# iPad_adapt_board.net
KiCad netlist of a schematic drawn in EAGLE
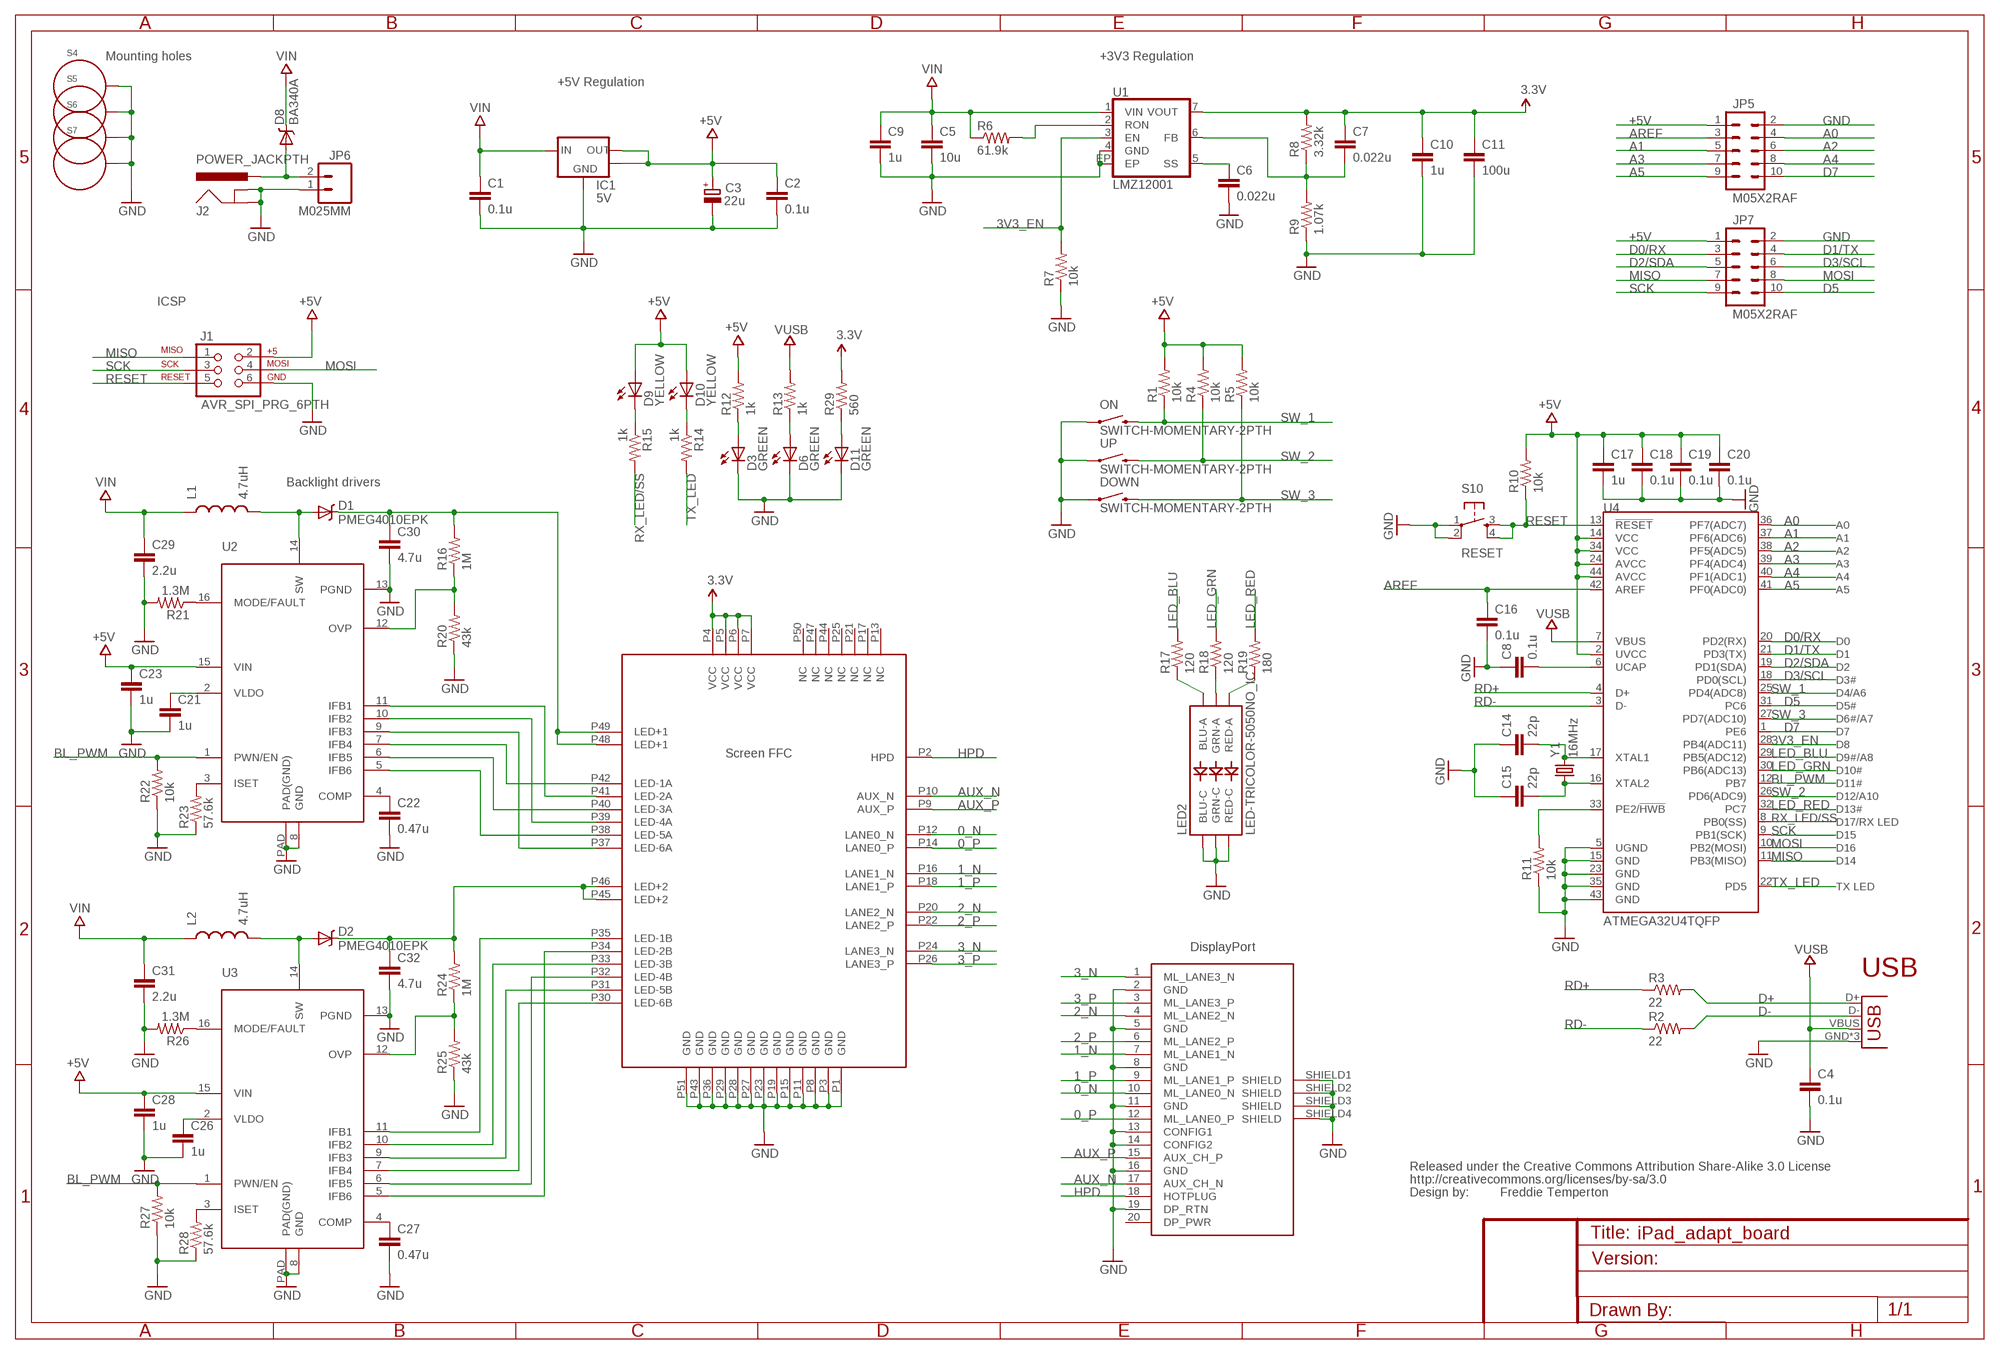
[diagram p0: schematic, sheet 1]

(export (version "E")
  (design (tool "Eeschema 10.0.6"))
  (components
    (comp (ref "C1")
      (value "0.1u")
      (footprint "eagle-import:0603-CAP")
      (libsource (lib "eagle-import") (part "SparkFun-Passives_CAP0603-CAP"))
    )
    (comp (ref "C2")
      (value "0.1u")
      (footprint "eagle-import:0603-CAP")
      (libsource (lib "eagle-import") (part "SparkFun-Passives_CAP0603-CAP"))
    )
    (comp (ref "C3")
      (value "22u")
      (footprint "eagle-import:SMC_B")
      (libsource (lib "eagle-import") (part "CPOL-EUSMCB"))
    )
    (comp (ref "C4")
      (value "0.1u")
      (footprint "eagle-import:0603-CAP")
      (libsource (lib "eagle-import") (part "SparkFun-Passives_CAP0603-CAP"))
    )
    (comp (ref "C5")
      (value "10u")
      (footprint "eagle-import:1206")
      (libsource (lib "eagle-import") (part "CAP1206"))
    )
    (comp (ref "C6")
      (value "0.022u")
      (footprint "eagle-import:0603-CAP")
      (libsource (lib "eagle-import") (part "SparkFun-Passives_CAP0603-CAP"))
    )
    (comp (ref "C7")
      (value "0.022u")
      (footprint "eagle-import:0603-CAP")
      (libsource (lib "eagle-import") (part "SparkFun-Passives_CAP0603-CAP"))
    )
    (comp (ref "C8")
      (value "0.1u")
      (footprint "eagle-import:0603-CAP")
      (libsource (lib "eagle-import") (part "SparkFun-Passives_CAP0603-CAP"))
    )
    (comp (ref "C9")
      (value "1u")
      (footprint "eagle-import:1206")
      (libsource (lib "eagle-import") (part "CAP1206"))
    )
    (comp (ref "C10")
      (value "1u")
      (footprint "eagle-import:1206")
      (libsource (lib "eagle-import") (part "CAP1206"))
    )
    (comp (ref "C11")
      (value "100u")
      (footprint "eagle-import:C1210")
      (libsource (lib "eagle-import") (part "C-EUC1210"))
    )
    (comp (ref "C14")
      (value "22p")
      (footprint "eagle-import:0603-CAP")
      (libsource (lib "eagle-import") (part "SparkFun-Passives_CAP0603-CAP"))
    )
    (comp (ref "C15")
      (value "22p")
      (footprint "eagle-import:0603-CAP")
      (libsource (lib "eagle-import") (part "SparkFun-Passives_CAP0603-CAP"))
    )
    (comp (ref "C16")
      (value "0.1u")
      (footprint "eagle-import:0603-CAP")
      (libsource (lib "eagle-import") (part "SparkFun-Passives_CAP0603-CAP"))
    )
    (comp (ref "C17")
      (value "1u")
      (footprint "eagle-import:0603-CAP")
      (libsource (lib "eagle-import") (part "SparkFun-Passives_CAP0603-CAP"))
    )
    (comp (ref "C18")
      (value "0.1u")
      (footprint "eagle-import:0603-CAP")
      (libsource (lib "eagle-import") (part "SparkFun-Passives_CAP0603-CAP"))
    )
    (comp (ref "C19")
      (value "0.1u")
      (footprint "eagle-import:0603-CAP")
      (libsource (lib "eagle-import") (part "SparkFun-Passives_CAP0603-CAP"))
    )
    (comp (ref "C20")
      (value "0.1u")
      (footprint "eagle-import:0603-CAP")
      (libsource (lib "eagle-import") (part "SparkFun-Passives_CAP0603-CAP"))
    )
    (comp (ref "C21")
      (value "1u")
      (footprint "eagle-import:0603-CAP")
      (libsource (lib "eagle-import") (part "SparkFun-Passives_CAP0603-CAP"))
    )
    (comp (ref "C22")
      (value "0.47u")
      (footprint "eagle-import:0603-CAP")
      (libsource (lib "eagle-import") (part "SparkFun-Passives_CAP0603-CAP"))
    )
    (comp (ref "C23")
      (value "1u")
      (footprint "eagle-import:0603-CAP")
      (libsource (lib "eagle-import") (part "SparkFun-Passives_CAP0603-CAP"))
    )
    (comp (ref "C26")
      (value "1u")
      (footprint "eagle-import:0603-CAP")
      (libsource (lib "eagle-import") (part "SparkFun-Passives_CAP0603-CAP"))
    )
    (comp (ref "C27")
      (value "0.47u")
      (footprint "eagle-import:0603-CAP")
      (libsource (lib "eagle-import") (part "SparkFun-Passives_CAP0603-CAP"))
    )
    (comp (ref "C28")
      (value "1u")
      (footprint "eagle-import:0603-CAP")
      (libsource (lib "eagle-import") (part "SparkFun-Passives_CAP0603-CAP"))
    )
    (comp (ref "C29")
      (value "2.2u")
      (footprint "eagle-import:0805")
      (libsource (lib "eagle-import") (part "CAP0805"))
    )
    (comp (ref "C30")
      (value "4.7u")
      (footprint "eagle-import:0805")
      (libsource (lib "eagle-import") (part "CAP0805"))
    )
    (comp (ref "C31")
      (value "2.2u")
      (footprint "eagle-import:0805")
      (libsource (lib "eagle-import") (part "CAP0805"))
    )
    (comp (ref "C32")
      (value "4.7u")
      (footprint "eagle-import:0805")
      (libsource (lib "eagle-import") (part "CAP0805"))
    )
    (comp (ref "CC_TEXT1")
      (value "CREATIVE_COMMONS")
      (footprint "eagle-import:CREATIVE_COMMONS")
      (libsource (lib "eagle-import") (part "CREATIVE_COMMONS"))
    )
    (comp (ref "D1")
      (value "PMEG4010EPK")
      (footprint "eagle-import:SOD1608")
      (libsource (lib "eagle-import") (part "PMEG4010EPK"))
    )
    (comp (ref "D2")
      (value "PMEG4010EPK")
      (footprint "eagle-import:SOD1608")
      (libsource (lib "eagle-import") (part "PMEG4010EPK"))
    )
    (comp (ref "D3")
      (value "GREEN")
      (footprint "eagle-import:LED-0603")
      (libsource (lib "eagle-import") (part "LED-GREEN0603"))
    )
    (comp (ref "D6")
      (value "GREEN")
      (footprint "eagle-import:LED-0603")
      (libsource (lib "eagle-import") (part "LED-GREEN0603"))
    )
    (comp (ref "D8")
      (value "BA340A")
      (footprint "eagle-import:SMA-DIODE")
      (libsource (lib "eagle-import") (part "B340A"))
    )
    (comp (ref "D9")
      (value "YELLOW")
      (footprint "eagle-import:LED-0603")
      (libsource (lib "eagle-import") (part "LED-YELLOW0603"))
    )
    (comp (ref "D10")
      (value "YELLOW")
      (footprint "eagle-import:LED-0603")
      (libsource (lib "eagle-import") (part "LED-YELLOW0603"))
    )
    (comp (ref "D11")
      (value "GREEN")
      (footprint "eagle-import:LED-0603")
      (libsource (lib "eagle-import") (part "LED-GREEN0603"))
    )
    (comp (ref "DOWN")
      (value "SWITCH-MOMENTARY-2PTH")
      (footprint "eagle-import:TACTILE-PTH")
      (libsource (lib "eagle-import") (part "SWITCH-MOMENTARY-2PTH"))
    )
    (comp (ref "IC1")
      (value "5V")
      (footprint "eagle-import:SOT223")
      (libsource (lib "eagle-import") (part "V_REG_LM1117SOT223"))
    )
    (comp (ref "J1")
      (value "AVR_SPI_PRG_6PTH")
      (footprint "eagle-import:2X3")
      (libsource (lib "eagle-import") (part "AVR_SPI_PRG_6PTH"))
    )
    (comp (ref "J2")
      (value "POWER_JACKPTH")
      (footprint "eagle-import:POWER_JACK_PTH")
      (libsource (lib "eagle-import") (part "POWER_JACKPTH"))
    )
    (comp (ref "J3") (value "DP") (footprint "eagle-import:DP") (libsource (lib "eagle-import") (part "DP")))
    (comp (ref "J4")
      (value "IPAD3-CONN")
      (footprint "eagle-import:MOLEX502250-5191")
      (libsource (lib "eagle-import") (part "IPAD3-CONN"))
    )
    (comp (ref "JP1")
      (value "USB-MICROB")
      (footprint "eagle-import:USB-MICROB")
      (libsource (lib "eagle-import") (part "USB-MICROB"))
    )
    (comp (ref "JP5")
      (value "M05X2RAF")
      (footprint "eagle-import:2X5-RAF")
      (libsource (lib "eagle-import") (part "M05X2RAF"))
    )
    (comp (ref "JP6")
      (value "M025MM")
      (footprint "eagle-import:SCREWTERMINAL-5MM-2")
      (libsource (lib "eagle-import") (part "M025MM"))
    )
    (comp (ref "JP7")
      (value "M05X2RAF")
      (footprint "eagle-import:2X5-RAF")
      (libsource (lib "eagle-import") (part "M05X2RAF"))
    )
    (comp (ref "L1")
      (value "4.7uH")
      (footprint "eagle-import:SRN6045")
      (libsource (lib "eagle-import") (part "INDUCTORBOURNS_SRN6045"))
    )
    (comp (ref "L2")
      (value "4.7uH")
      (footprint "eagle-import:SRN6045")
      (libsource (lib "eagle-import") (part "INDUCTORBOURNS_SRN6045"))
    )
    (comp (ref "LED2")
      (value "LED-TRICOLOR-5050NO_IC")
      (footprint "eagle-import:LED-TRICOLOR-5050")
      (libsource (lib "eagle-import") (part "LED-TRICOLOR-5050NO_IC"))
    )
    (comp (ref "ON")
      (value "SWITCH-MOMENTARY-2PTH")
      (footprint "eagle-import:TACTILE-PTH")
      (libsource (lib "eagle-import") (part "SWITCH-MOMENTARY-2PTH"))
    )
    (comp (ref "R1")
      (value "10k")
      (footprint "eagle-import:0603-RES")
      (libsource (lib "eagle-import") (part "RESISTOR0603-RES"))
    )
    (comp (ref "R2")
      (value "22")
      (footprint "eagle-import:0603-RES")
      (libsource (lib "eagle-import") (part "RESISTOR0603-RES"))
    )
    (comp (ref "R3")
      (value "22")
      (footprint "eagle-import:0603-RES")
      (libsource (lib "eagle-import") (part "RESISTOR0603-RES"))
    )
    (comp (ref "R4")
      (value "10k")
      (footprint "eagle-import:0603-RES")
      (libsource (lib "eagle-import") (part "RESISTOR0603-RES"))
    )
    (comp (ref "R5")
      (value "10k")
      (footprint "eagle-import:0603-RES")
      (libsource (lib "eagle-import") (part "RESISTOR0603-RES"))
    )
    (comp (ref "R6")
      (value "61.9k")
      (footprint "eagle-import:0603-RES")
      (libsource (lib "eagle-import") (part "RESISTOR0603-RES"))
    )
    (comp (ref "R7")
      (value "10k")
      (footprint "eagle-import:0603-RES")
      (libsource (lib "eagle-import") (part "RESISTOR0603-RES"))
    )
    (comp (ref "R8")
      (value "3.32k")
      (footprint "eagle-import:0603-RES")
      (libsource (lib "eagle-import") (part "RESISTOR0603-RES"))
    )
    (comp (ref "R9")
      (value "1.07k")
      (footprint "eagle-import:0603-RES")
      (libsource (lib "eagle-import") (part "RESISTOR0603-RES"))
    )
    (comp (ref "R10")
      (value "10k")
      (footprint "eagle-import:0603-RES")
      (libsource (lib "eagle-import") (part "RESISTOR0603-RES"))
    )
    (comp (ref "R11")
      (value "10k")
      (footprint "eagle-import:0603-RES")
      (libsource (lib "eagle-import") (part "RESISTOR0603-RES"))
    )
    (comp (ref "R12")
      (value "1k")
      (footprint "eagle-import:0603-RES")
      (libsource (lib "eagle-import") (part "RESISTOR0603-RES"))
    )
    (comp (ref "R13")
      (value "1k")
      (footprint "eagle-import:0603-RES")
      (libsource (lib "eagle-import") (part "RESISTOR0603-RES"))
    )
    (comp (ref "R14")
      (value "1k")
      (footprint "eagle-import:0603-RES")
      (libsource (lib "eagle-import") (part "RESISTOR0603-RES"))
    )
    (comp (ref "R15")
      (value "1k")
      (footprint "eagle-import:0603-RES")
      (libsource (lib "eagle-import") (part "RESISTOR0603-RES"))
    )
    (comp (ref "R16")
      (value "1M")
      (footprint "eagle-import:0603-RES")
      (libsource (lib "eagle-import") (part "RESISTOR0603-RES"))
    )
    (comp (ref "R17")
      (value "120")
      (footprint "eagle-import:0603-RES")
      (libsource (lib "eagle-import") (part "RESISTOR0603-RES"))
    )
    (comp (ref "R18")
      (value "120")
      (footprint "eagle-import:0603-RES")
      (libsource (lib "eagle-import") (part "RESISTOR0603-RES"))
    )
    (comp (ref "R19")
      (value "180")
      (footprint "eagle-import:0603-RES")
      (libsource (lib "eagle-import") (part "RESISTOR0603-RES"))
    )
    (comp (ref "R20")
      (value "43k")
      (footprint "eagle-import:0603-RES")
      (libsource (lib "eagle-import") (part "RESISTOR0603-RES"))
    )
    (comp (ref "R21")
      (value "1.3M")
      (footprint "eagle-import:0603-RES")
      (libsource (lib "eagle-import") (part "RESISTOR0603-RES"))
    )
    (comp (ref "R22")
      (value "10k")
      (footprint "eagle-import:0603-RES")
      (libsource (lib "eagle-import") (part "RESISTOR0603-RES"))
    )
    (comp (ref "R23")
      (value "57.6k")
      (footprint "eagle-import:0603-RES")
      (libsource (lib "eagle-import") (part "RESISTOR0603-RES"))
    )
    (comp (ref "R24")
      (value "1M")
      (footprint "eagle-import:0603-RES")
      (libsource (lib "eagle-import") (part "RESISTOR0603-RES"))
    )
    (comp (ref "R25")
      (value "43k")
      (footprint "eagle-import:0603-RES")
      (libsource (lib "eagle-import") (part "RESISTOR0603-RES"))
    )
    (comp (ref "R26")
      (value "1.3M")
      (footprint "eagle-import:0603-RES")
      (libsource (lib "eagle-import") (part "RESISTOR0603-RES"))
    )
    (comp (ref "R27")
      (value "10k")
      (footprint "eagle-import:0603-RES")
      (libsource (lib "eagle-import") (part "RESISTOR0603-RES"))
    )
    (comp (ref "R28")
      (value "57.6k")
      (footprint "eagle-import:0603-RES")
      (libsource (lib "eagle-import") (part "RESISTOR0603-RES"))
    )
    (comp (ref "R29")
      (value "560")
      (footprint "eagle-import:0603-RES")
      (libsource (lib "eagle-import") (part "RESISTOR0603-RES"))
    )
    (comp (ref "S4")
      (value "STANDOFF_ELECTRICAL")
      (footprint "eagle-import:STANDOFF-ELECTRICAL")
      (libsource (lib "eagle-import") (part "STANDOFF_ELECTRICAL"))
    )
    (comp (ref "S5")
      (value "STANDOFF_ELECTRICAL")
      (footprint "eagle-import:STANDOFF-ELECTRICAL")
      (libsource (lib "eagle-import") (part "STANDOFF_ELECTRICAL"))
    )
    (comp (ref "S6")
      (value "STANDOFF_ELECTRICAL")
      (footprint "eagle-import:STANDOFF-ELECTRICAL")
      (libsource (lib "eagle-import") (part "STANDOFF_ELECTRICAL"))
    )
    (comp (ref "S7")
      (value "STANDOFF_ELECTRICAL")
      (footprint "eagle-import:STANDOFF-ELECTRICAL")
      (libsource (lib "eagle-import") (part "STANDOFF_ELECTRICAL"))
    )
    (comp (ref "S10")
      (value "RESET")
      (footprint "eagle-import:TACTILE_SWITCH_SMD")
      (libsource (lib "eagle-import") (part "TAC_SWITCHSMD"))
    )
    (comp (ref "U1")
      (value "LMZ12001")
      (footprint "eagle-import:TO-PMOD-7")
      (libsource (lib "eagle-import") (part "LMZ14203"))
    )
    (comp (ref "U2")
      (value "TPS61176")
      (footprint "eagle-import:QFN16")
      (libsource (lib "eagle-import") (part "TPS61176"))
    )
    (comp (ref "U3")
      (value "TPS61176")
      (footprint "eagle-import:QFN16")
      (libsource (lib "eagle-import") (part "TPS61176"))
    )
    (comp (ref "U4")
      (value "ATMEGA32U4TQFP")
      (footprint "eagle-import:SPARKFUN-DIGITALIC_TQFP44")
      (libsource (lib "eagle-import") (part "ATMEGA32U4TQFP"))
    )
    (comp (ref "UP")
      (value "SWITCH-MOMENTARY-2PTH")
      (footprint "eagle-import:TACTILE-PTH")
      (libsource (lib "eagle-import") (part "SWITCH-MOMENTARY-2PTH"))
    )
    (comp (ref "Y1")
      (value "16MHz")
      (footprint "eagle-import:CRYSTAL-TXC-7A")
      (libsource (lib "eagle-import") (part "CRYSTALTXC-7A"))
    )
  )
  (nets
    (net (code "1") (name "+5V") (class "Default")
      (node (ref "C17") (pin "1") (pinfunction "1_1") (pintype "passive"))
      (node (ref "C18") (pin "1") (pinfunction "1_1") (pintype "passive"))
      (node (ref "C19") (pin "1") (pinfunction "1_1") (pintype "passive"))
      (node (ref "C2") (pin "1") (pinfunction "1_1") (pintype "passive"))
      (node (ref "C20") (pin "1") (pinfunction "1_1") (pintype "passive"))
      (node (ref "C23") (pin "1") (pinfunction "1_1") (pintype "passive"))
      (node (ref "C28") (pin "1") (pinfunction "1_1") (pintype "passive"))
      (node (ref "C3") (pin "+") (pinfunction "+_+") (pintype "passive"))
      (node (ref "D10") (pin "A") (pinfunction "A_A") (pintype "passive"))
      (node (ref "D9") (pin "A") (pinfunction "A_A") (pintype "passive"))
      (node (ref "IC1") (pin "2") (pinfunction "OUT_2") (pintype "power_in"))
      (node (ref "IC1") (pin "4") (pinfunction "OUT_4") (pintype "power_in"))
      (node (ref "J1") (pin "2") (pinfunction "2_2") (pintype "passive"))
      (node (ref "JP5") (pin "1") (pinfunction "1_1") (pintype "passive"))
      (node (ref "JP7") (pin "1") (pinfunction "1_1") (pintype "passive"))
      (node (ref "R1") (pin "2") (pinfunction "2_2") (pintype "passive"))
      (node (ref "R10") (pin "2") (pinfunction "2_2") (pintype "passive"))
      (node (ref "R12") (pin "2") (pinfunction "2_2") (pintype "passive"))
      (node (ref "R4") (pin "2") (pinfunction "2_2") (pintype "passive"))
      (node (ref "R5") (pin "2") (pinfunction "2_2") (pintype "passive"))
      (node (ref "U2") (pin "15") (pinfunction "VIN_15") (pintype "bidirectional"))
      (node (ref "U3") (pin "15") (pinfunction "VIN_15") (pintype "bidirectional"))
      (node (ref "U4") (pin "14") (pinfunction "VCC_14") (pintype "bidirectional"))
      (node (ref "U4") (pin "2") (pinfunction "UVCC_2") (pintype "bidirectional"))
      (node (ref "U4") (pin "24") (pinfunction "AVCC_24") (pintype "bidirectional"))
      (node (ref "U4") (pin "34") (pinfunction "VCC_34") (pintype "bidirectional"))
      (node (ref "U4") (pin "44") (pinfunction "AVCC_44") (pintype "bidirectional"))
    )
    (net (code "2") (name "/0_N") (class "Default")
      (node (ref "J3") (pin "10") (pinfunction "ML_LANE0_N_10") (pintype "bidirectional"))
      (node (ref "J4") (pin "P12") (pinfunction "LANE0_N_P12") (pintype "bidirectional"))
    )
    (net (code "3") (name "/0_P") (class "Default")
      (node (ref "J3") (pin "12") (pinfunction "ML_LANE0_P_12") (pintype "bidirectional"))
      (node (ref "J4") (pin "P14") (pinfunction "LANE0_P_P14") (pintype "bidirectional"))
    )
    (net (code "4") (name "/1_N") (class "Default")
      (node (ref "J3") (pin "7") (pinfunction "ML_LANE1_N_7") (pintype "bidirectional"))
      (node (ref "J4") (pin "P16") (pinfunction "LANE1_N_P16") (pintype "bidirectional"))
    )
    (net (code "5") (name "/1_P") (class "Default")
      (node (ref "J3") (pin "9") (pinfunction "ML_LANE1_P_9") (pintype "bidirectional"))
      (node (ref "J4") (pin "P18") (pinfunction "LANE1_P_P18") (pintype "bidirectional"))
    )
    (net (code "6") (name "/2_N") (class "Default")
      (node (ref "J3") (pin "4") (pinfunction "ML_LANE2_N_4") (pintype "bidirectional"))
      (node (ref "J4") (pin "P20") (pinfunction "LANE2_N_P20") (pintype "bidirectional"))
    )
    (net (code "7") (name "/2_P") (class "Default")
      (node (ref "J3") (pin "6") (pinfunction "ML_LANE2_P_6") (pintype "bidirectional"))
      (node (ref "J4") (pin "P22") (pinfunction "LANE2_P_P22") (pintype "bidirectional"))
    )
    (net (code "8") (name "/3V3_EN") (class "Default")
      (node (ref "R7") (pin "2") (pinfunction "2_2") (pintype "passive"))
      (node (ref "U1") (pin "3") (pinfunction "EN_3") (pintype "bidirectional"))
      (node (ref "U4") (pin "28") (pinfunction "PB4(ADC11)_28") (pintype "bidirectional"))
    )
    (net (code "9") (name "/3_N") (class "Default")
      (node (ref "J3") (pin "1") (pinfunction "ML_LANE3_N_1") (pintype "bidirectional"))
      (node (ref "J4") (pin "P24") (pinfunction "LANE3_N_P24") (pintype "bidirectional"))
    )
    (net (code "10") (name "/3_P") (class "Default")
      (node (ref "J3") (pin "3") (pinfunction "ML_LANE3_P_3") (pintype "bidirectional"))
      (node (ref "J4") (pin "P26") (pinfunction "LANE3_P_P26") (pintype "bidirectional"))
    )
    (net (code "11") (name "/A0") (class "Default")
      (node (ref "JP5") (pin "4") (pinfunction "4_4") (pintype "passive"))
      (node (ref "U4") (pin "36") (pinfunction "PF7(ADC7)_36") (pintype "bidirectional"))
    )
    (net (code "12") (name "/A1") (class "Default")
      (node (ref "JP5") (pin "5") (pinfunction "5_5") (pintype "passive"))
      (node (ref "U4") (pin "37") (pinfunction "PF6(ADC6)_37") (pintype "bidirectional"))
    )
    (net (code "13") (name "/A2") (class "Default")
      (node (ref "JP5") (pin "6") (pinfunction "6_6") (pintype "passive"))
      (node (ref "U4") (pin "38") (pinfunction "PF5(ADC5)_38") (pintype "bidirectional"))
    )
    (net (code "14") (name "/A3") (class "Default")
      (node (ref "JP5") (pin "7") (pinfunction "7_7") (pintype "passive"))
      (node (ref "U4") (pin "39") (pinfunction "PF4(ADC4)_39") (pintype "bidirectional"))
    )
    (net (code "15") (name "/A4") (class "Default")
      (node (ref "JP5") (pin "8") (pinfunction "8_8") (pintype "passive"))
      (node (ref "U4") (pin "40") (pinfunction "PF1(ADC1)_40") (pintype "bidirectional"))
    )
    (net (code "16") (name "/A5") (class "Default")
      (node (ref "JP5") (pin "9") (pinfunction "9_9") (pintype "passive"))
      (node (ref "U4") (pin "41") (pinfunction "PF0(ADC0)_41") (pintype "bidirectional"))
    )
    (net (code "17") (name "/AREF") (class "Default")
      (node (ref "C16") (pin "1") (pinfunction "1_1") (pintype "passive"))
      (node (ref "JP5") (pin "3") (pinfunction "3_3") (pintype "passive"))
      (node (ref "U4") (pin "42") (pinfunction "AREF_42") (pintype "bidirectional"))
    )
    (net (code "18") (name "/AUX_N") (class "Default")
      (node (ref "J3") (pin "17") (pinfunction "AUX_CH_N_17") (pintype "bidirectional"))
      (node (ref "J4") (pin "P10") (pinfunction "AUX_N_P10") (pintype "bidirectional"))
    )
    (net (code "19") (name "/AUX_P") (class "Default")
      (node (ref "J3") (pin "15") (pinfunction "AUX_CH_P_15") (pintype "bidirectional"))
      (node (ref "J4") (pin "P9") (pinfunction "AUX_P_P9") (pintype "bidirectional"))
    )
    (net (code "20") (name "/BL_PWM") (class "Default")
      (node (ref "R22") (pin "2") (pinfunction "2_2") (pintype "passive"))
      (node (ref "R27") (pin "2") (pinfunction "2_2") (pintype "passive"))
      (node (ref "U2") (pin "1") (pinfunction "PWN/EN_1") (pintype "bidirectional"))
      (node (ref "U3") (pin "1") (pinfunction "PWN/EN_1") (pintype "bidirectional"))
      (node (ref "U4") (pin "12") (pinfunction "PB7_12") (pintype "bidirectional"))
    )
    (net (code "21") (name "/D+") (class "Default")
      (node (ref "JP1") (pin "D+") (pinfunction "D+_D+") (pintype "bidirectional"))
      (node (ref "R3") (pin "2") (pinfunction "2_2") (pintype "passive"))
    )
    (net (code "22") (name "/D-") (class "Default")
      (node (ref "JP1") (pin "D-") (pinfunction "D-_D-") (pintype "bidirectional"))
      (node (ref "R2") (pin "2") (pinfunction "2_2") (pintype "passive"))
    )
    (net (code "23") (name "/D0{slash}RX") (class "Default")
      (node (ref "JP7") (pin "3") (pinfunction "3_3") (pintype "passive"))
      (node (ref "U4") (pin "20") (pinfunction "PD2(RX)_20") (pintype "bidirectional"))
    )
    (net (code "24") (name "/D1{slash}TX") (class "Default")
      (node (ref "JP7") (pin "4") (pinfunction "4_4") (pintype "passive"))
      (node (ref "U4") (pin "21") (pinfunction "PD3(TX)_21") (pintype "bidirectional"))
    )
    (net (code "25") (name "/D2{slash}SDA") (class "Default")
      (node (ref "JP7") (pin "5") (pinfunction "5_5") (pintype "passive"))
      (node (ref "U4") (pin "19") (pinfunction "PD1(SDA)_19") (pintype "bidirectional"))
    )
    (net (code "26") (name "/D3{slash}SCL") (class "Default")
      (node (ref "JP7") (pin "6") (pinfunction "6_6") (pintype "passive"))
      (node (ref "U4") (pin "18") (pinfunction "PD0(SCL)_18") (pintype "bidirectional"))
    )
    (net (code "27") (name "/D5") (class "Default")
      (node (ref "JP7") (pin "10") (pinfunction "10_10") (pintype "passive"))
      (node (ref "U4") (pin "31") (pinfunction "PC6_31") (pintype "bidirectional"))
    )
    (net (code "28") (name "/D7") (class "Default")
      (node (ref "JP5") (pin "10") (pinfunction "10_10") (pintype "passive"))
      (node (ref "U4") (pin "1") (pinfunction "PE6_1") (pintype "bidirectional"))
    )
    (net (code "29") (name "/HPD") (class "Default")
      (node (ref "J3") (pin "18") (pinfunction "HOTPLUG_18") (pintype "bidirectional"))
      (node (ref "J4") (pin "P2") (pinfunction "HPD_P2") (pintype "bidirectional"))
    )
    (net (code "30") (name "/LED_BLU") (class "Default")
      (node (ref "R17") (pin "2") (pinfunction "2_2") (pintype "passive"))
      (node (ref "U4") (pin "29") (pinfunction "PB5(ADC12)_29") (pintype "bidirectional"))
    )
    (net (code "31") (name "/LED_GRN") (class "Default")
      (node (ref "R18") (pin "2") (pinfunction "2_2") (pintype "passive"))
      (node (ref "U4") (pin "30") (pinfunction "PB6(ADC13)_30") (pintype "bidirectional"))
    )
    (net (code "32") (name "/LED_RED") (class "Default")
      (node (ref "R19") (pin "2") (pinfunction "2_2") (pintype "passive"))
      (node (ref "U4") (pin "32") (pinfunction "PC7_32") (pintype "bidirectional"))
    )
    (net (code "33") (name "/MISO") (class "Default")
      (node (ref "J1") (pin "1") (pinfunction "1_1") (pintype "passive"))
      (node (ref "JP7") (pin "7") (pinfunction "7_7") (pintype "passive"))
      (node (ref "U4") (pin "11") (pinfunction "PB3(MISO)_11") (pintype "bidirectional"))
    )
    (net (code "34") (name "/MOSI") (class "Default")
      (node (ref "J1") (pin "4") (pinfunction "4_4") (pintype "passive"))
      (node (ref "JP7") (pin "8") (pinfunction "8_8") (pintype "passive"))
      (node (ref "U4") (pin "10") (pinfunction "PB2(MOSI)_10") (pintype "bidirectional"))
    )
    (net (code "35") (name "/RD+") (class "Default")
      (node (ref "R3") (pin "1") (pinfunction "1_1") (pintype "passive"))
      (node (ref "U4") (pin "4") (pinfunction "D+_4") (pintype "bidirectional"))
    )
    (net (code "36") (name "/RD-") (class "Default")
      (node (ref "R2") (pin "1") (pinfunction "1_1") (pintype "passive"))
      (node (ref "U4") (pin "3") (pinfunction "D-_3") (pintype "bidirectional"))
    )
    (net (code "37") (name "/RESET") (class "Default")
      (node (ref "J1") (pin "5") (pinfunction "5_5") (pintype "passive"))
      (node (ref "R10") (pin "1") (pinfunction "1_1") (pintype "passive"))
      (node (ref "S10") (pin "3") (pinfunction "3_3") (pintype "passive"))
      (node (ref "S10") (pin "4") (pinfunction "4_4") (pintype "passive"))
      (node (ref "U4") (pin "13") (pinfunction "~{RESET}_13") (pintype "bidirectional"))
    )
    (net (code "38") (name "/RX_LED{slash}SS") (class "Default")
      (node (ref "R15") (pin "2") (pinfunction "2_2") (pintype "passive"))
      (node (ref "U4") (pin "8") (pinfunction "PB0(SS)_8") (pintype "bidirectional"))
    )
    (net (code "39") (name "/SCK") (class "Default")
      (node (ref "J1") (pin "3") (pinfunction "3_3") (pintype "passive"))
      (node (ref "JP7") (pin "9") (pinfunction "9_9") (pintype "passive"))
      (node (ref "U4") (pin "9") (pinfunction "PB1(SCK)_9") (pintype "bidirectional"))
    )
    (net (code "40") (name "/SW_1") (class "Default")
      (node (ref "ON") (pin "3") (pinfunction "2_3") (pintype "passive"))
      (node (ref "R1") (pin "1") (pinfunction "1_1") (pintype "passive"))
      (node (ref "U4") (pin "25") (pinfunction "PD4(ADC8)_25") (pintype "bidirectional"))
    )
    (net (code "41") (name "/SW_2") (class "Default")
      (node (ref "R4") (pin "1") (pinfunction "1_1") (pintype "passive"))
      (node (ref "U4") (pin "26") (pinfunction "PD6(ADC9)_26") (pintype "bidirectional"))
      (node (ref "UP") (pin "3") (pinfunction "2_3") (pintype "passive"))
    )
    (net (code "42") (name "/SW_3") (class "Default")
      (node (ref "DOWN") (pin "3") (pinfunction "2_3") (pintype "passive"))
      (node (ref "R5") (pin "1") (pinfunction "1_1") (pintype "passive"))
      (node (ref "U4") (pin "27") (pinfunction "PD7(ADC10)_27") (pintype "bidirectional"))
    )
    (net (code "43") (name "/TX_LED") (class "Default")
      (node (ref "R14") (pin "2") (pinfunction "2_2") (pintype "passive"))
      (node (ref "U4") (pin "22") (pinfunction "PD5_22") (pintype "bidirectional"))
    )
    (net (code "44") (name "3.3V") (class "Default")
      (node (ref "C10") (pin "1") (pinfunction "1_1") (pintype "passive"))
      (node (ref "C11") (pin "1") (pinfunction "1_1") (pintype "passive"))
      (node (ref "C7") (pin "1") (pinfunction "1_1") (pintype "passive"))
      (node (ref "J4") (pin "P4") (pinfunction "VCC_P4") (pintype "bidirectional"))
      (node (ref "J4") (pin "P5") (pinfunction "VCC_P5") (pintype "bidirectional"))
      (node (ref "J4") (pin "P6") (pinfunction "VCC_P6") (pintype "bidirectional"))
      (node (ref "J4") (pin "P7") (pinfunction "VCC_P7") (pintype "bidirectional"))
      (node (ref "R29") (pin "2") (pinfunction "2_2") (pintype "passive"))
      (node (ref "R8") (pin "2") (pinfunction "2_2") (pintype "passive"))
      (node (ref "U1") (pin "7") (pinfunction "VOUT_7") (pintype "bidirectional"))
    )
    (net (code "45") (name "GND") (class "Default")
      (node (ref "C1") (pin "2") (pinfunction "2_2") (pintype "passive"))
      (node (ref "C10") (pin "2") (pinfunction "2_2") (pintype "passive"))
      (node (ref "C11") (pin "2") (pinfunction "2_2") (pintype "passive"))
      (node (ref "C14") (pin "1") (pinfunction "1_1") (pintype "passive"))
      (node (ref "C15") (pin "1") (pinfunction "1_1") (pintype "passive"))
      (node (ref "C16") (pin "2") (pinfunction "2_2") (pintype "passive"))
      (node (ref "C17") (pin "2") (pinfunction "2_2") (pintype "passive"))
      (node (ref "C18") (pin "2") (pinfunction "2_2") (pintype "passive"))
      (node (ref "C19") (pin "2") (pinfunction "2_2") (pintype "passive"))
      (node (ref "C2") (pin "2") (pinfunction "2_2") (pintype "passive"))
      (node (ref "C20") (pin "2") (pinfunction "2_2") (pintype "passive"))
      (node (ref "C21") (pin "2") (pinfunction "2_2") (pintype "passive"))
      (node (ref "C22") (pin "2") (pinfunction "2_2") (pintype "passive"))
      (node (ref "C23") (pin "2") (pinfunction "2_2") (pintype "passive"))
      (node (ref "C26") (pin "2") (pinfunction "2_2") (pintype "passive"))
      (node (ref "C27") (pin "2") (pinfunction "2_2") (pintype "passive"))
      (node (ref "C28") (pin "2") (pinfunction "2_2") (pintype "passive"))
      (node (ref "C29") (pin "2") (pinfunction "2_2") (pintype "passive"))
      (node (ref "C3") (pin "-") (pinfunction "-_-") (pintype "passive"))
      (node (ref "C30") (pin "2") (pinfunction "2_2") (pintype "passive"))
      (node (ref "C31") (pin "2") (pinfunction "2_2") (pintype "passive"))
      (node (ref "C32") (pin "2") (pinfunction "2_2") (pintype "passive"))
      (node (ref "C4") (pin "2") (pinfunction "2_2") (pintype "passive"))
      (node (ref "C5") (pin "2") (pinfunction "2_2") (pintype "passive"))
      (node (ref "C6") (pin "2") (pinfunction "2_2") (pintype "passive"))
      (node (ref "C8") (pin "1") (pinfunction "1_1") (pintype "passive"))
      (node (ref "C9") (pin "2") (pinfunction "2_2") (pintype "passive"))
      (node (ref "D11") (pin "C") (pinfunction "C_C") (pintype "passive"))
      (node (ref "D3") (pin "C") (pinfunction "C_C") (pintype "passive"))
      (node (ref "D6") (pin "C") (pinfunction "C_C") (pintype "passive"))
      (node (ref "DOWN") (pin "1") (pinfunction "1_1") (pintype "passive"))
      (node (ref "IC1") (pin "1") (pinfunction "ADJ_1") (pintype "input"))
      (node (ref "J1") (pin "6") (pinfunction "6_6") (pintype "passive"))
      (node (ref "J2") (pin "GND") (pinfunction "GND_GND") (pintype "bidirectional"))
      (node (ref "J2") (pin "GNDBREAK") (pinfunction "GNDBREAK_GNDBREAK") (pintype "bidirectional"))
      (node (ref "J3") (pin "11") (pinfunction "GND_11") (pintype "bidirectional"))
      (node (ref "J3") (pin "13") (pinfunction "CONFIG1_13") (pintype "bidirectional"))
      (node (ref "J3") (pin "14") (pinfunction "CONFIG2_14") (pintype "bidirectional"))
      (node (ref "J3") (pin "16") (pinfunction "GND_16") (pintype "bidirectional"))
      (node (ref "J3") (pin "19") (pinfunction "DP_RTN_19") (pintype "bidirectional"))
      (node (ref "J3") (pin "2") (pinfunction "GND_2") (pintype "bidirectional"))
      (node (ref "J3") (pin "5") (pinfunction "GND_5") (pintype "bidirectional"))
      (node (ref "J3") (pin "8") (pinfunction "GND_8") (pintype "bidirectional"))
      (node (ref "J3") (pin "SHIELD1") (pinfunction "SHIELD_SHIELD1") (pintype "bidirectional"))
      (node (ref "J3") (pin "SHIELD2") (pinfunction "SHIELD_SHIELD2") (pintype "bidirectional"))
      (node (ref "J3") (pin "SHIELD3") (pinfunction "SHIELD_SHIELD3") (pintype "bidirectional"))
      (node (ref "J3") (pin "SHIELD4") (pinfunction "SHIELD_SHIELD4") (pintype "bidirectional"))
      (node (ref "J4") (pin "P1") (pinfunction "GND_P1") (pintype "bidirectional"))
      (node (ref "J4") (pin "P11") (pinfunction "GND_P11") (pintype "bidirectional"))
      (node (ref "J4") (pin "P15") (pinfunction "GND_P15") (pintype "bidirectional"))
      (node (ref "J4") (pin "P19") (pinfunction "GND_P19") (pintype "bidirectional"))
      (node (ref "J4") (pin "P23") (pinfunction "GND_P23") (pintype "bidirectional"))
      (node (ref "J4") (pin "P27") (pinfunction "GND_P27") (pintype "bidirectional"))
      (node (ref "J4") (pin "P28") (pinfunction "GND_P28") (pintype "bidirectional"))
      (node (ref "J4") (pin "P29") (pinfunction "GND_P29") (pintype "bidirectional"))
      (node (ref "J4") (pin "P3") (pinfunction "GND_P3") (pintype "bidirectional"))
      (node (ref "J4") (pin "P36") (pinfunction "GND_P36") (pintype "bidirectional"))
      (node (ref "J4") (pin "P43") (pinfunction "GND_P43") (pintype "bidirectional"))
      (node (ref "J4") (pin "P51") (pinfunction "GND_P51") (pintype "bidirectional"))
      (node (ref "J4") (pin "P8") (pinfunction "GND_P8") (pintype "bidirectional"))
      (node (ref "JP1") (pin "GND") (pinfunction "GND_GND") (pintype "bidirectional"))
      (node (ref "JP1") (pin "MT1") (pinfunction "GND_MT1") (pintype "bidirectional"))
      (node (ref "JP1") (pin "MT2") (pinfunction "GND_MT2") (pintype "bidirectional"))
      (node (ref "JP5") (pin "2") (pinfunction "2_2") (pintype "passive"))
      (node (ref "JP6") (pin "1") (pinfunction "1_1") (pintype "passive"))
      (node (ref "JP7") (pin "2") (pinfunction "2_2") (pintype "passive"))
      (node (ref "LED2") (pin "4") (pinfunction "BLU-C_4") (pintype "bidirectional"))
      (node (ref "LED2") (pin "5") (pinfunction "RED-C_5") (pintype "bidirectional"))
      (node (ref "LED2") (pin "6") (pinfunction "GRN-C_6") (pintype "bidirectional"))
      (node (ref "ON") (pin "1") (pinfunction "1_1") (pintype "passive"))
      (node (ref "R11") (pin "1") (pinfunction "1_1") (pintype "passive"))
      (node (ref "R20") (pin "1") (pinfunction "1_1") (pintype "passive"))
      (node (ref "R21") (pin "2") (pinfunction "2_2") (pintype "passive"))
      (node (ref "R22") (pin "1") (pinfunction "1_1") (pintype "passive"))
      (node (ref "R23") (pin "1") (pinfunction "1_1") (pintype "passive"))
      (node (ref "R25") (pin "1") (pinfunction "1_1") (pintype "passive"))
      (node (ref "R26") (pin "2") (pinfunction "2_2") (pintype "passive"))
      (node (ref "R27") (pin "1") (pinfunction "1_1") (pintype "passive"))
      (node (ref "R28") (pin "1") (pinfunction "1_1") (pintype "passive"))
      (node (ref "R7") (pin "1") (pinfunction "1_1") (pintype "passive"))
      (node (ref "R9") (pin "1") (pinfunction "1_1") (pintype "passive"))
      (node (ref "S10") (pin "1") (pinfunction "1_1") (pintype "passive"))
      (node (ref "S10") (pin "2") (pinfunction "2_2") (pintype "passive"))
      (node (ref "S4") (pin "P1") (pinfunction "P$1_P1") (pintype "bidirectional"))
      (node (ref "S5") (pin "P1") (pinfunction "P$1_P1") (pintype "bidirectional"))
      (node (ref "S6") (pin "P1") (pinfunction "P$1_P1") (pintype "bidirectional"))
      (node (ref "S7") (pin "P1") (pinfunction "P$1_P1") (pintype "bidirectional"))
      (node (ref "U1") (pin "4") (pinfunction "GND_4") (pintype "bidirectional"))
      (node (ref "U1") (pin "EP") (pinfunction "EP_EP") (pintype "bidirectional"))
      (node (ref "U2") (pin "13") (pinfunction "PGND_13") (pintype "bidirectional"))
      (node (ref "U2") (pin "8") (pinfunction "GND_8") (pintype "bidirectional"))
      (node (ref "U2") (pin "PAD") (pinfunction "PAD(GND)_PAD") (pintype "bidirectional"))
      (node (ref "U3") (pin "13") (pinfunction "PGND_13") (pintype "bidirectional"))
      (node (ref "U3") (pin "8") (pinfunction "GND_8") (pintype "bidirectional"))
      (node (ref "U3") (pin "PAD") (pinfunction "PAD(GND)_PAD") (pintype "bidirectional"))
      (node (ref "U4") (pin "15") (pinfunction "GND_15") (pintype "bidirectional"))
      (node (ref "U4") (pin "23") (pinfunction "GND_23") (pintype "bidirectional"))
      (node (ref "U4") (pin "35") (pinfunction "GND_35") (pintype "bidirectional"))
      (node (ref "U4") (pin "43") (pinfunction "GND_43") (pintype "bidirectional"))
      (node (ref "U4") (pin "5") (pinfunction "UGND_5") (pintype "bidirectional"))
      (node (ref "UP") (pin "1") (pinfunction "1_1") (pintype "passive"))
    )
    (net (code "46") (name "Net-(C30-Pad1)") (class "Default")
      (node (ref "C30") (pin "1") (pinfunction "1_1") (pintype "passive"))
      (node (ref "D1") (pin "C") (pinfunction "C_C") (pintype "passive"))
      (node (ref "J4") (pin "P48") (pinfunction "LED+1_P48") (pintype "bidirectional"))
      (node (ref "J4") (pin "P49") (pinfunction "LED+1_P49") (pintype "bidirectional"))
      (node (ref "R16") (pin "2") (pinfunction "2_2") (pintype "passive"))
    )
    (net (code "47") (name "Net-(C32-Pad1)") (class "Default")
      (node (ref "C32") (pin "1") (pinfunction "1_1") (pintype "passive"))
      (node (ref "D2") (pin "C") (pinfunction "C_C") (pintype "passive"))
      (node (ref "J4") (pin "P45") (pinfunction "LED+2_P45") (pintype "bidirectional"))
      (node (ref "J4") (pin "P46") (pinfunction "LED+2_P46") (pintype "bidirectional"))
      (node (ref "R24") (pin "2") (pinfunction "2_2") (pintype "passive"))
    )
    (net (code "48") (name "Net-(D3-PadA)") (class "Default")
      (node (ref "D3") (pin "A") (pinfunction "A_A") (pintype "passive"))
      (node (ref "R12") (pin "1") (pinfunction "1_1") (pintype "passive"))
    )
    (net (code "49") (name "Net-(D6-PadA)") (class "Default")
      (node (ref "D6") (pin "A") (pinfunction "A_A") (pintype "passive"))
      (node (ref "R13") (pin "1") (pinfunction "1_1") (pintype "passive"))
    )
    (net (code "50") (name "Net-(D8-PadA)") (class "Default")
      (node (ref "D8") (pin "A") (pinfunction "A_A") (pintype "passive"))
      (node (ref "J2") (pin "PWR") (pinfunction "PWR_PWR") (pintype "bidirectional"))
      (node (ref "JP6") (pin "2") (pinfunction "2_2") (pintype "passive"))
    )
    (net (code "51") (name "Net-(D9-PadC)") (class "Default")
      (node (ref "D9") (pin "C") (pinfunction "C_C") (pintype "passive"))
      (node (ref "R15") (pin "1") (pinfunction "1_1") (pintype "passive"))
    )
    (net (code "52") (name "Net-(D10-PadC)") (class "Default")
      (node (ref "D10") (pin "C") (pinfunction "C_C") (pintype "passive"))
      (node (ref "R14") (pin "1") (pinfunction "1_1") (pintype "passive"))
    )
    (net (code "53") (name "Net-(D11-PadA)") (class "Default")
      (node (ref "D11") (pin "A") (pinfunction "A_A") (pintype "passive"))
      (node (ref "R29") (pin "1") (pinfunction "1_1") (pintype "passive"))
    )
    (net (code "54") (name "Net-(J4-LED-1A)") (class "Default")
      (node (ref "J4") (pin "P42") (pinfunction "LED-1A_P42") (pintype "bidirectional"))
      (node (ref "U2") (pin "7") (pinfunction "IFB4_7") (pintype "bidirectional"))
    )
    (net (code "55") (name "Net-(J4-LED-1B)") (class "Default")
      (node (ref "J4") (pin "P35") (pinfunction "LED-1B_P35") (pintype "bidirectional"))
      (node (ref "U3") (pin "11") (pinfunction "IFB1_11") (pintype "bidirectional"))
    )
    (net (code "56") (name "Net-(J4-LED-2A)") (class "Default")
      (node (ref "J4") (pin "P41") (pinfunction "LED-2A_P41") (pintype "bidirectional"))
      (node (ref "U2") (pin "11") (pinfunction "IFB1_11") (pintype "bidirectional"))
    )
    (net (code "57") (name "Net-(J4-LED-2B)") (class "Default")
      (node (ref "J4") (pin "P34") (pinfunction "LED-2B_P34") (pintype "bidirectional"))
      (node (ref "U3") (pin "5") (pinfunction "IFB6_5") (pintype "bidirectional"))
    )
    (net (code "58") (name "Net-(J4-LED-3A)") (class "Default")
      (node (ref "J4") (pin "P40") (pinfunction "LED-3A_P40") (pintype "bidirectional"))
      (node (ref "U2") (pin "6") (pinfunction "IFB5_6") (pintype "bidirectional"))
    )
    (net (code "59") (name "Net-(J4-LED-3B)") (class "Default")
      (node (ref "J4") (pin "P33") (pinfunction "LED-3B_P33") (pintype "bidirectional"))
      (node (ref "U3") (pin "10") (pinfunction "IFB2_10") (pintype "bidirectional"))
    )
    (net (code "60") (name "Net-(J4-LED-4A)") (class "Default")
      (node (ref "J4") (pin "P39") (pinfunction "LED-4A_P39") (pintype "bidirectional"))
      (node (ref "U2") (pin "10") (pinfunction "IFB2_10") (pintype "bidirectional"))
    )
    (net (code "61") (name "Net-(J4-LED-4B)") (class "Default")
      (node (ref "J4") (pin "P32") (pinfunction "LED-4B_P32") (pintype "bidirectional"))
      (node (ref "U3") (pin "6") (pinfunction "IFB5_6") (pintype "bidirectional"))
    )
    (net (code "62") (name "Net-(J4-LED-5A)") (class "Default")
      (node (ref "J4") (pin "P38") (pinfunction "LED-5A_P38") (pintype "bidirectional"))
      (node (ref "U2") (pin "5") (pinfunction "IFB6_5") (pintype "bidirectional"))
    )
    (net (code "63") (name "Net-(J4-LED-5B)") (class "Default")
      (node (ref "J4") (pin "P31") (pinfunction "LED-5B_P31") (pintype "bidirectional"))
      (node (ref "U3") (pin "9") (pinfunction "IFB3_9") (pintype "bidirectional"))
    )
    (net (code "64") (name "Net-(J4-LED-6A)") (class "Default")
      (node (ref "J4") (pin "P37") (pinfunction "LED-6A_P37") (pintype "bidirectional"))
      (node (ref "U2") (pin "9") (pinfunction "IFB3_9") (pintype "bidirectional"))
    )
    (net (code "65") (name "Net-(J4-LED-6B)") (class "Default")
      (node (ref "J4") (pin "P30") (pinfunction "LED-6B_P30") (pintype "bidirectional"))
      (node (ref "U3") (pin "7") (pinfunction "IFB4_7") (pintype "bidirectional"))
    )
    (net (code "66") (name "Net-(LED2-BLU-A)") (class "Default")
      (node (ref "LED2") (pin "3") (pinfunction "BLU-A_3") (pintype "bidirectional"))
      (node (ref "R17") (pin "1") (pinfunction "1_1") (pintype "passive"))
    )
    (net (code "67") (name "Net-(LED2-GRN-A)") (class "Default")
      (node (ref "LED2") (pin "1") (pinfunction "GRN-A_1") (pintype "bidirectional"))
      (node (ref "R18") (pin "1") (pinfunction "1_1") (pintype "passive"))
    )
    (net (code "68") (name "Net-(LED2-RED-A)") (class "Default")
      (node (ref "LED2") (pin "2") (pinfunction "RED-A_2") (pintype "bidirectional"))
      (node (ref "R19") (pin "1") (pinfunction "1_1") (pintype "passive"))
    )
    (net (code "69") (name "Net-(U1-FB)") (class "Default")
      (node (ref "C7") (pin "2") (pinfunction "2_2") (pintype "passive"))
      (node (ref "R8") (pin "1") (pinfunction "1_1") (pintype "passive"))
      (node (ref "R9") (pin "2") (pinfunction "2_2") (pintype "passive"))
      (node (ref "U1") (pin "6") (pinfunction "FB_6") (pintype "bidirectional"))
    )
    (net (code "70") (name "Net-(U1-RON)") (class "Default")
      (node (ref "R6") (pin "2") (pinfunction "2_2") (pintype "passive"))
      (node (ref "U1") (pin "2") (pinfunction "RON_2") (pintype "bidirectional"))
    )
    (net (code "71") (name "Net-(U1-SS)") (class "Default")
      (node (ref "C6") (pin "1") (pinfunction "1_1") (pintype "passive"))
      (node (ref "U1") (pin "5") (pinfunction "SS_5") (pintype "bidirectional"))
    )
    (net (code "72") (name "Net-(U2-COMP)") (class "Default")
      (node (ref "C22") (pin "1") (pinfunction "1_1") (pintype "passive"))
      (node (ref "U2") (pin "4") (pinfunction "COMP_4") (pintype "bidirectional"))
    )
    (net (code "73") (name "Net-(U2-ISET)") (class "Default")
      (node (ref "R23") (pin "2") (pinfunction "2_2") (pintype "passive"))
      (node (ref "U2") (pin "3") (pinfunction "ISET_3") (pintype "bidirectional"))
    )
    (net (code "74") (name "Net-(U2-MODE{slash}FAULT)") (class "Default")
      (node (ref "R21") (pin "1") (pinfunction "1_1") (pintype "passive"))
      (node (ref "U2") (pin "16") (pinfunction "MODE/FAULT_16") (pintype "bidirectional"))
    )
    (net (code "75") (name "Net-(U2-OVP)") (class "Default")
      (node (ref "R16") (pin "1") (pinfunction "1_1") (pintype "passive"))
      (node (ref "R20") (pin "2") (pinfunction "2_2") (pintype "passive"))
      (node (ref "U2") (pin "12") (pinfunction "OVP_12") (pintype "bidirectional"))
    )
    (net (code "76") (name "Net-(U2-SW)") (class "Default")
      (node (ref "D1") (pin "A") (pinfunction "A_A") (pintype "passive"))
      (node (ref "L1") (pin "2") (pinfunction "2_2") (pintype "passive"))
      (node (ref "U2") (pin "14") (pinfunction "SW_14") (pintype "bidirectional"))
    )
    (net (code "77") (name "Net-(U2-VLDO)") (class "Default")
      (node (ref "C21") (pin "1") (pinfunction "1_1") (pintype "passive"))
      (node (ref "U2") (pin "2") (pinfunction "VLDO_2") (pintype "bidirectional"))
    )
    (net (code "78") (name "Net-(U3-COMP)") (class "Default")
      (node (ref "C27") (pin "1") (pinfunction "1_1") (pintype "passive"))
      (node (ref "U3") (pin "4") (pinfunction "COMP_4") (pintype "bidirectional"))
    )
    (net (code "79") (name "Net-(U3-ISET)") (class "Default")
      (node (ref "R28") (pin "2") (pinfunction "2_2") (pintype "passive"))
      (node (ref "U3") (pin "3") (pinfunction "ISET_3") (pintype "bidirectional"))
    )
    (net (code "80") (name "Net-(U3-MODE{slash}FAULT)") (class "Default")
      (node (ref "R26") (pin "1") (pinfunction "1_1") (pintype "passive"))
      (node (ref "U3") (pin "16") (pinfunction "MODE/FAULT_16") (pintype "bidirectional"))
    )
    (net (code "81") (name "Net-(U3-OVP)") (class "Default")
      (node (ref "R24") (pin "1") (pinfunction "1_1") (pintype "passive"))
      (node (ref "R25") (pin "2") (pinfunction "2_2") (pintype "passive"))
      (node (ref "U3") (pin "12") (pinfunction "OVP_12") (pintype "bidirectional"))
    )
    (net (code "82") (name "Net-(U3-SW)") (class "Default")
      (node (ref "D2") (pin "A") (pinfunction "A_A") (pintype "passive"))
      (node (ref "L2") (pin "2") (pinfunction "2_2") (pintype "passive"))
      (node (ref "U3") (pin "14") (pinfunction "SW_14") (pintype "bidirectional"))
    )
    (net (code "83") (name "Net-(U3-VLDO)") (class "Default")
      (node (ref "C26") (pin "1") (pinfunction "1_1") (pintype "passive"))
      (node (ref "U3") (pin "2") (pinfunction "VLDO_2") (pintype "bidirectional"))
    )
    (net (code "84") (name "Net-(U4-PE2{slash}~{HWB})") (class "Default")
      (node (ref "R11") (pin "2") (pinfunction "2_2") (pintype "passive"))
      (node (ref "U4") (pin "33") (pinfunction "PE2/~{HWB}_33") (pintype "bidirectional"))
    )
    (net (code "85") (name "Net-(U4-UCAP)") (class "Default")
      (node (ref "C8") (pin "2") (pinfunction "2_2") (pintype "passive"))
      (node (ref "U4") (pin "6") (pinfunction "UCAP_6") (pintype "bidirectional"))
    )
    (net (code "86") (name "Net-(U4-XTAL1)") (class "Default")
      (node (ref "C14") (pin "2") (pinfunction "2_2") (pintype "passive"))
      (node (ref "U4") (pin "17") (pinfunction "XTAL1_17") (pintype "bidirectional"))
      (node (ref "Y1") (pin "P$2") (pinfunction "2_P$2") (pintype "passive"))
    )
    (net (code "87") (name "Net-(U4-XTAL2)") (class "Default")
      (node (ref "C15") (pin "2") (pinfunction "2_2") (pintype "passive"))
      (node (ref "U4") (pin "16") (pinfunction "XTAL2_16") (pintype "bidirectional"))
      (node (ref "Y1") (pin "P$1") (pinfunction "1_P$1") (pintype "passive"))
    )
    (net (code "88") (name "VIN") (class "Default")
      (node (ref "C1") (pin "1") (pinfunction "1_1") (pintype "passive"))
      (node (ref "C29") (pin "1") (pinfunction "1_1") (pintype "passive"))
      (node (ref "C31") (pin "1") (pinfunction "1_1") (pintype "passive"))
      (node (ref "C5") (pin "1") (pinfunction "1_1") (pintype "passive"))
      (node (ref "C9") (pin "1") (pinfunction "1_1") (pintype "passive"))
      (node (ref "D8") (pin "C") (pinfunction "C_C") (pintype "passive"))
      (node (ref "IC1") (pin "3") (pinfunction "IN_3") (pintype "input"))
      (node (ref "L1") (pin "1") (pinfunction "1_1") (pintype "passive"))
      (node (ref "L2") (pin "1") (pinfunction "1_1") (pintype "passive"))
      (node (ref "R6") (pin "1") (pinfunction "1_1") (pintype "passive"))
      (node (ref "U1") (pin "1") (pinfunction "VIN_1") (pintype "bidirectional"))
    )
    (net (code "89") (name "VUSB") (class "Default")
      (node (ref "C4") (pin "1") (pinfunction "1_1") (pintype "passive"))
      (node (ref "JP1") (pin "VBUS") (pinfunction "VBUS_VBUS") (pintype "bidirectional"))
      (node (ref "R13") (pin "2") (pinfunction "2_2") (pintype "passive"))
      (node (ref "U4") (pin "7") (pinfunction "VBUS_7") (pintype "bidirectional"))
    )
    (net (code "90") (name "unconnected-(J3-DP_PWR-Pad20)") (class "Default")
      (node (ref "J3") (pin "20") (pinfunction "DP_PWR_20") (pintype "bidirectional"))
    )
    (net (code "91") (name "unconnected-(J4-NC-PadP13)") (class "Default")
      (node (ref "J4") (pin "P13") (pinfunction "NC_P13") (pintype "bidirectional"))
    )
    (net (code "92") (name "unconnected-(J4-NC-PadP17)") (class "Default")
      (node (ref "J4") (pin "P17") (pinfunction "NC_P17") (pintype "bidirectional"))
    )
    (net (code "93") (name "unconnected-(J4-NC-PadP21)") (class "Default")
      (node (ref "J4") (pin "P21") (pinfunction "NC_P21") (pintype "bidirectional"))
    )
    (net (code "94") (name "unconnected-(J4-NC-PadP25)") (class "Default")
      (node (ref "J4") (pin "P25") (pinfunction "NC_P25") (pintype "bidirectional"))
    )
    (net (code "95") (name "unconnected-(J4-NC-PadP44)") (class "Default")
      (node (ref "J4") (pin "P44") (pinfunction "NC_P44") (pintype "bidirectional"))
    )
    (net (code "96") (name "unconnected-(J4-NC-PadP47)") (class "Default")
      (node (ref "J4") (pin "P47") (pinfunction "NC_P47") (pintype "bidirectional"))
    )
    (net (code "97") (name "unconnected-(J4-NC-PadP50)") (class "Default")
      (node (ref "J4") (pin "P50") (pinfunction "NC_P50") (pintype "bidirectional"))
    )
  )
)
